# EOG_FRONT_END.net
KiCad netlist of a schematic drawn in Altium Designer
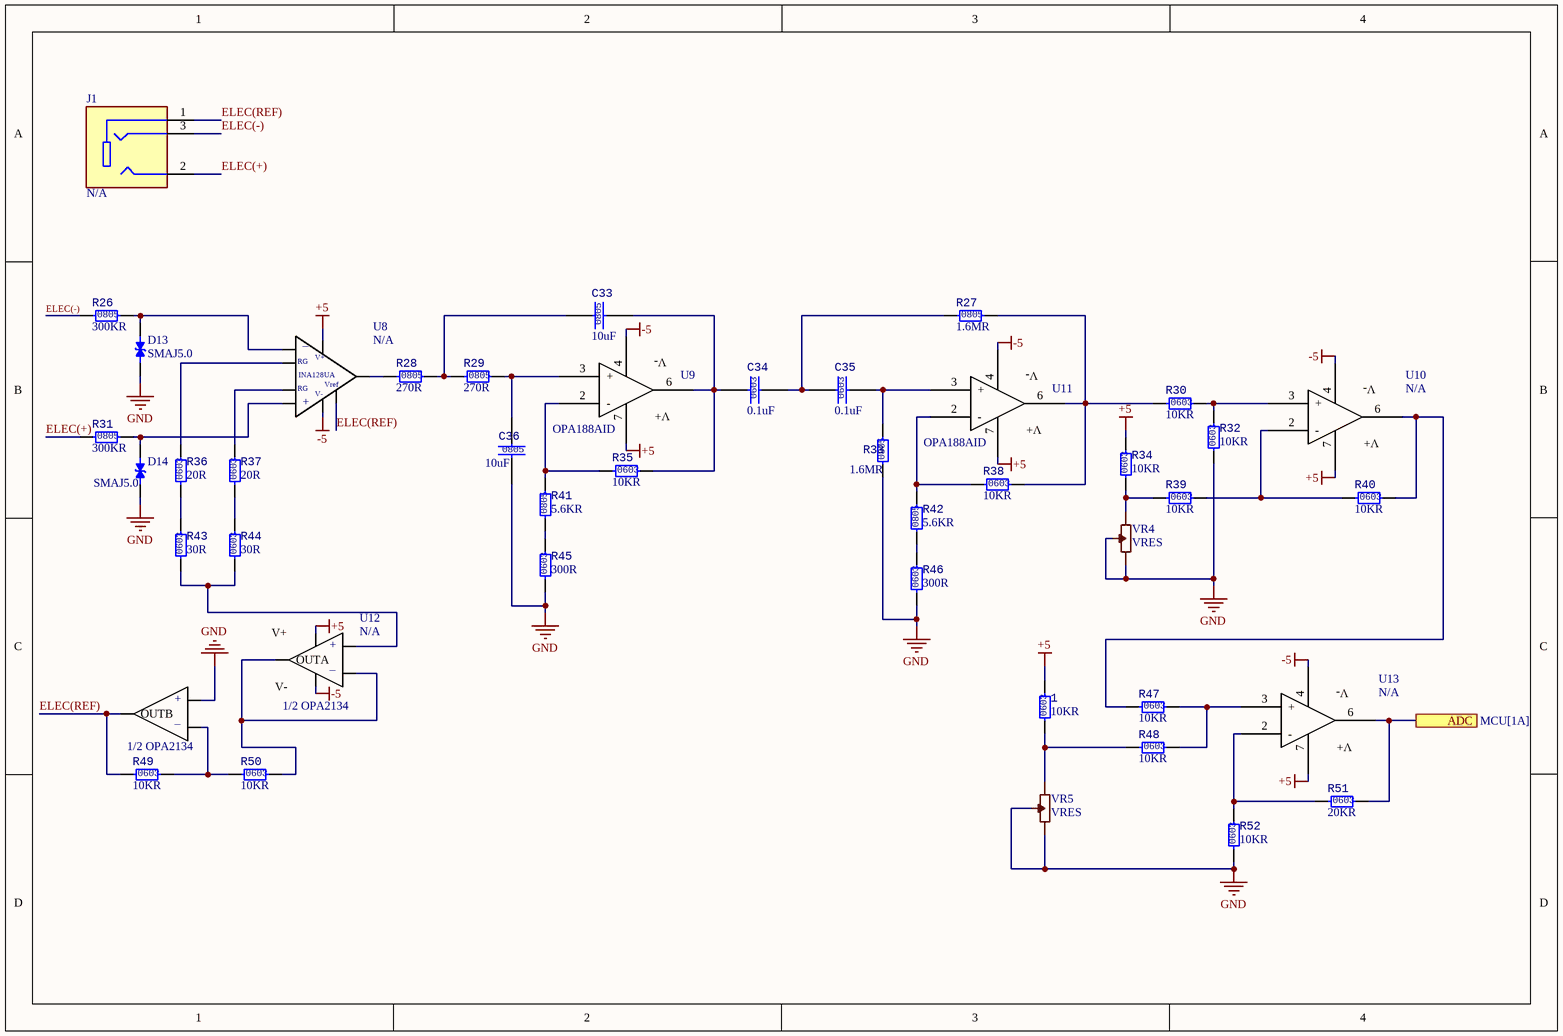
[diagram p0: EOG_FRONT_END.SchDoc]

(export (version "E")
  (design (tool "Eeschema 10.0.6"))
  (components
    (comp (ref "1")
      (value "10KR")
      (footprint "RESC 0603(1608) SMD")
      (description "RESISTOR SMD 10KR OHM 1% 100mW 0603")
      (fields (field (name "SIZE") "0603") (field (name "TOLERANCE") "1%"))
      (libsource (lib "Database_Libs1") (part "RESISTOR"))
    )
    (comp (ref "C33")
      (value "10uF")
      (footprint "CAPCER 0603 SMD")
      (description "CAPACITOR SMD 10uF 25V 10% 0805")
      (fields (field (name "SIZE") "0805") (field (name "TOLERANCE") "10%"))
      (libsource (lib "Database_Libs1") (part "CAPACITOR"))
    )
    (comp (ref "C34")
      (value "0.1uF")
      (footprint "CAPCER 0805 SMD")
      (description "CAPACITOR SMD 0.1uF 50V 10% 0603")
      (fields (field (name "SIZE") "0603") (field (name "TOLERANCE") "10%"))
      (libsource (lib "Database_Libs1") (part "CAPACITOR"))
    )
    (comp (ref "C35")
      (value "0.1uF")
      (footprint "CAPCER 0805 SMD")
      (description "CAPACITOR SMD 0.1uF 50V 10% 0603")
      (fields (field (name "SIZE") "0603") (field (name "TOLERANCE") "10%"))
      (libsource (lib "Database_Libs1") (part "CAPACITOR"))
    )
    (comp (ref "C36")
      (value "10uF")
      (footprint "CAPCER 0603 SMD")
      (description "CAPACITOR SMD 10uF 25V 10% 0805")
      (fields (field (name "SIZE") "0805") (field (name "TOLERANCE") "10%"))
      (libsource (lib "Database_Libs1") (part "CAPACITOR"))
    )
    (comp (ref "D13") (value "SMAJ5.0") (libsource (lib "Database_Libs1") (part "SMAJ5.0")))
    (comp (ref "D14") (value "SMAJ5.0") (libsource (lib "Database_Libs1") (part "SMAJ5.0")))
    (comp (ref "J1")
      (value "N/A")
      (footprint "JACK_3.5")
      (description "Jack Audio 3.5mm PJ-320D PJ320D Hàn Board chân dán")
      (fields (field (name "Comment") "JACK 3.5mm"))
      (libsource (lib "Database_Libs1") (part "JACK_3.5"))
    )
    (comp (ref "R26")
      (value "300KR")
      (footprint "RESC 0805 SMD")
      (description "RESISTOR SMD 300KR OHM 5% 125mW 0805")
      (fields (field (name "SIZE") "0805") (field (name "TOLERANCE") "5%"))
      (libsource (lib "") (part "RESISTOR_1"))
    )
    (comp (ref "R27")
      (value "1.6MR")
      (footprint "RESC 0805 SMD")
      (description "RESISTOR SMD 1.6MR OHM 5% 125mW 0805")
      (fields (field (name "SIZE") "0805") (field (name "TOLERANCE") "5%"))
      (libsource (lib "") (part "RESISTOR_1"))
    )
    (comp (ref "R28")
      (value "270R")
      (footprint "RESC 0805 SMD")
      (description "RESISTOR SMD 270R OHM 5% 125mW 0805")
      (fields (field (name "SIZE") "0805") (field (name "TOLERANCE") "5%"))
      (libsource (lib "") (part "RESISTOR_1"))
    )
    (comp (ref "R29")
      (value "270R")
      (footprint "RESC 0805 SMD")
      (description "RESISTOR SMD 270R OHM 5% 125mW 0805")
      (fields (field (name "SIZE") "0805") (field (name "TOLERANCE") "5%"))
      (libsource (lib "") (part "RESISTOR_1"))
    )
    (comp (ref "R30")
      (value "10KR")
      (footprint "RESC 0603(1608) SMD")
      (description "RESISTOR SMD 10KR OHM 1% 100mW 0603")
      (fields (field (name "SIZE") "0603") (field (name "TOLERANCE") "1%"))
      (libsource (lib "") (part "RESISTOR_1"))
    )
    (comp (ref "R31")
      (value "300KR")
      (footprint "RESC 0805 SMD")
      (description "RESISTOR SMD 300KR OHM 5% 125mW 0805")
      (fields (field (name "SIZE") "0805") (field (name "TOLERANCE") "5%"))
      (libsource (lib "") (part "RESISTOR_1"))
    )
    (comp (ref "R32")
      (value "10KR")
      (footprint "RESC 0603(1608) SMD")
      (description "RESISTOR SMD 10KR OHM 1% 100mW 0603")
      (fields (field (name "SIZE") "0603") (field (name "TOLERANCE") "1%"))
      (libsource (lib "Database_Libs1") (part "RESISTOR"))
    )
    (comp (ref "R33")
      (value "1.6MR")
      (footprint "RESC 0805 SMD")
      (description "RESISTOR SMD 1.6MR OHM 5% 125mW 0805")
      (fields (field (name "SIZE") "0805") (field (name "TOLERANCE") "5%"))
      (libsource (lib "Database_Libs1") (part "RESISTOR"))
    )
    (comp (ref "R34")
      (value "10KR")
      (footprint "RESC 0603(1608) SMD")
      (description "RESISTOR SMD 10KR OHM 1% 100mW 0603")
      (fields (field (name "SIZE") "0603") (field (name "TOLERANCE") "1%"))
      (libsource (lib "Database_Libs1") (part "RESISTOR"))
    )
    (comp (ref "R35")
      (value "10KR")
      (footprint "RESC 0603(1608) SMD")
      (description "RESISTOR SMD 10KR OHM 1% 100mW 0603")
      (fields (field (name "SIZE") "0603") (field (name "TOLERANCE") "1%"))
      (libsource (lib "") (part "RESISTOR_1"))
    )
    (comp (ref "R36")
      (value "20R")
      (footprint "RESC 0603(1608) SMD")
      (description "RESISTOR SMD 510R OHM 1% 100mW 0603")
      (fields (field (name "SIZE") "0603") (field (name "TOLERANCE") "1%") (field (name "Comment") "510R"))
      (libsource (lib "Database_Libs1") (part "RESISTOR"))
    )
    (comp (ref "R37")
      (value "20R")
      (footprint "RESC 0603(1608) SMD")
      (description "RESISTOR SMD 510R OHM 1% 100mW 0603")
      (fields (field (name "SIZE") "0603") (field (name "TOLERANCE") "1%") (field (name "Comment") "510R"))
      (libsource (lib "Database_Libs1") (part "RESISTOR"))
    )
    (comp (ref "R38")
      (value "10KR")
      (footprint "RESC 0603(1608) SMD")
      (description "RESISTOR SMD 10KR OHM 1% 100mW 0603")
      (fields (field (name "SIZE") "0603") (field (name "TOLERANCE") "1%"))
      (libsource (lib "") (part "RESISTOR_1"))
    )
    (comp (ref "R39")
      (value "10KR")
      (footprint "RESC 0603(1608) SMD")
      (description "RESISTOR SMD 10KR OHM 1% 100mW 0603")
      (fields (field (name "SIZE") "0603") (field (name "TOLERANCE") "1%"))
      (libsource (lib "") (part "RESISTOR_1"))
    )
    (comp (ref "R40")
      (value "10KR")
      (footprint "RESC 0603(1608) SMD")
      (description "RESISTOR SMD 10KR OHM 1% 100mW 0603")
      (fields (field (name "SIZE") "0603") (field (name "TOLERANCE") "1%"))
      (libsource (lib "") (part "RESISTOR_1"))
    )
    (comp (ref "R41")
      (value "5.6KR")
      (footprint "RESC 0805 SMD")
      (description "RESISTOR SMD 5.6KR OHM 1% 125mW 0805")
      (fields (field (name "SIZE") "0805") (field (name "TOLERANCE") "1%"))
      (libsource (lib "Database_Libs1") (part "RESISTOR"))
    )
    (comp (ref "R42")
      (value "5.6KR")
      (footprint "RESC 0805 SMD")
      (description "RESISTOR SMD 5.6KR OHM 1% 125mW 0805")
      (fields (field (name "SIZE") "0805") (field (name "TOLERANCE") "1%"))
      (libsource (lib "Database_Libs1") (part "RESISTOR"))
    )
    (comp (ref "R43")
      (value "30R")
      (footprint "RESC 0603(1608) SMD")
      (description "RESISTOR SMD 12KR OHM 1% 100mW 0603")
      (fields (field (name "SIZE") "0603") (field (name "TOLERANCE") "1%") (field (name "Comment") "12KR"))
      (libsource (lib "Database_Libs1") (part "RESISTOR"))
    )
    (comp (ref "R44")
      (value "30R")
      (footprint "RESC 0603(1608) SMD")
      (description "RESISTOR SMD 12KR OHM 1% 100mW 0603")
      (fields (field (name "SIZE") "0603") (field (name "TOLERANCE") "1%") (field (name "Comment") "12KR"))
      (libsource (lib "Database_Libs1") (part "RESISTOR"))
    )
    (comp (ref "R45")
      (value "300R")
      (footprint "RESC 0603(1608) SMD")
      (description "RESISTOR SMD 300R OHM 1% 125mW 0603")
      (fields (field (name "SIZE") "0603") (field (name "TOLERANCE") "1%"))
      (libsource (lib "Database_Libs1") (part "RESISTOR"))
    )
    (comp (ref "R46")
      (value "300R")
      (footprint "RESC 0603(1608) SMD")
      (description "RESISTOR SMD 300R OHM 1% 125mW 0603")
      (fields (field (name "SIZE") "0603") (field (name "TOLERANCE") "1%"))
      (libsource (lib "Database_Libs1") (part "RESISTOR"))
    )
    (comp (ref "R47")
      (value "10KR")
      (footprint "RESC 0603(1608) SMD")
      (description "RESISTOR SMD 10KR OHM 1% 100mW 0603")
      (fields (field (name "SIZE") "0603") (field (name "TOLERANCE") "1%"))
      (libsource (lib "") (part "RESISTOR_1"))
    )
    (comp (ref "R48")
      (value "10KR")
      (footprint "RESC 0603(1608) SMD")
      (description "RESISTOR SMD 10KR OHM 1% 100mW 0603")
      (fields (field (name "SIZE") "0603") (field (name "TOLERANCE") "1%"))
      (libsource (lib "") (part "RESISTOR_1"))
    )
    (comp (ref "R49")
      (value "10KR")
      (footprint "RESC 0603(1608) SMD")
      (description "RESISTOR SMD 10KR OHM 1% 100mW 0603")
      (fields (field (name "SIZE") "0603") (field (name "TOLERANCE") "1%"))
      (libsource (lib "") (part "RESISTOR_1"))
    )
    (comp (ref "R50")
      (value "10KR")
      (footprint "RESC 0603(1608) SMD")
      (description "RESISTOR SMD 10KR OHM 1% 100mW 0603")
      (fields (field (name "SIZE") "0603") (field (name "TOLERANCE") "1%"))
      (libsource (lib "") (part "RESISTOR_1"))
    )
    (comp (ref "R51")
      (value "20KR")
      (footprint "RESC 0603(1608) SMD")
      (description "RESISTOR SMD 10KR OHM 1% 100mW 0603")
      (fields (field (name "SIZE") "0603") (field (name "TOLERANCE") "1%") (field (name "Comment") "10KR"))
      (libsource (lib "") (part "RESISTOR_1"))
    )
    (comp (ref "R52")
      (value "10KR")
      (footprint "RESC 0603(1608) SMD")
      (description "RESISTOR SMD 10KR OHM 1% 100mW 0603")
      (fields (field (name "SIZE") "0603") (field (name "TOLERANCE") "1%"))
      (libsource (lib "Database_Libs1") (part "RESISTOR"))
    )
    (comp (ref "U8")
      (value "N/A")
      (footprint "8-SOIC")
      (description "Instrumentation Amplifier 1 Circuit 8-SOIC")
      (fields (field (name "Comment") "INA128UA"))
      (libsource (lib "Database_Libs1") (part "INA128UA"))
    )
    (comp (ref "U9")
      (value "OPA188AID")
      (footprint "8-SOIC")
      (description "Zero-Drift Amplifier 1 Circuit Rail-to-Rail 8-SOIC")
      (libsource (lib "Database_Libs1") (part "OPA188AID"))
    )
    (comp (ref "U10")
      (value "N/A")
      (footprint "8-SOIC")
      (description "Zero-Drift Amplifier 1 Circuit Rail-to-Rail 8-SOIC")
      (fields (field (name "Comment") "OPA188AID"))
      (libsource (lib "Database_Libs1") (part "OPA188AID"))
    )
    (comp (ref "U11")
      (value "OPA188AID")
      (footprint "8-SOIC")
      (description "Zero-Drift Amplifier 1 Circuit Rail-to-Rail 8-SOIC")
      (libsource (lib "Database_Libs1") (part "OPA188AID"))
    )
    (comp (ref "U12")
      (value "N/A")
      (footprint "8-SOIC")
      (description "IC AUDIO 2 CIRCUIT 8SOIC")
      (fields (field (name "Comment") "OPA2134UA"))
      (libsource (lib "Database_Libs1") (part "OPA2134UA"))
    )
    (comp (ref "U13")
      (value "N/A")
      (footprint "8-SOIC")
      (description "Zero-Drift Amplifier 1 Circuit Rail-to-Rail 8-SOIC")
      (fields (field (name "Comment") "OPA188AID"))
      (libsource (lib "Database_Libs1") (part "OPA188AID"))
    )
    (comp (ref "VR4") (value "VRES") (libsource (lib "Database_Libs1") (part "VRES")))
    (comp (ref "VR5") (value "VRES") (libsource (lib "Database_Libs1") (part "VRES")))
  )
  (nets
    (net (code "1") (name "+5") (class "Default")
      (node (ref "1") (pin "2") (pinfunction "2_2") (pintype "passive"))
      (node (ref "R34") (pin "2") (pinfunction "2_2") (pintype "passive"))
      (node (ref "U10") (pin "7") (pinfunction "VCC_7") (pintype "passive"))
      (node (ref "U11") (pin "7") (pinfunction "VCC_7") (pintype "passive"))
      (node (ref "U12") (pin "8") (pinfunction "V+_8") (pintype "passive"))
      (node (ref "U13") (pin "7") (pinfunction "VCC_7") (pintype "passive"))
      (node (ref "U8") (pin "7") (pinfunction "9_7") (pintype "passive"))
      (node (ref "U9") (pin "7") (pinfunction "VCC_7") (pintype "passive"))
    )
    (net (code "2") (name "-5") (class "Default")
      (node (ref "U10") (pin "4") (pinfunction "GND_4") (pintype "passive"))
      (node (ref "U11") (pin "4") (pinfunction "GND_4") (pintype "passive"))
      (node (ref "U12") (pin "4") (pinfunction "V-_4") (pintype "passive"))
      (node (ref "U13") (pin "4") (pinfunction "GND_4") (pintype "passive"))
      (node (ref "U8") (pin "4") (pinfunction "10_4") (pintype "passive"))
      (node (ref "U9") (pin "4") (pinfunction "GND_4") (pintype "passive"))
    )
    (net (code "3") (name "/ADC") (class "Default")
      (node (ref "R51") (pin "2") (pinfunction "2_2") (pintype "passive"))
      (node (ref "U13") (pin "6") (pinfunction "OUT_1_6") (pintype "passive"))
    )
    (net (code "4") (name "/ELEC(+)") (class "Default")
      (node (ref "J1") (pin "2") (pinfunction "2_2") (pintype "passive"))
      (node (ref "R31") (pin "1") (pinfunction "1_1") (pintype "passive"))
    )
    (net (code "5") (name "/ELEC(-)") (class "Default")
      (node (ref "J1") (pin "3") (pinfunction "3_3") (pintype "passive"))
      (node (ref "R26") (pin "1") (pinfunction "1_1") (pintype "passive"))
    )
    (net (code "6") (name "/ELEC(REF)") (class "Default")
      (node (ref "J1") (pin "1") (pinfunction "1_1") (pintype "passive"))
      (node (ref "R49") (pin "1") (pinfunction "1_1") (pintype "passive"))
      (node (ref "U12") (pin "7") (pinfunction "OUTB_7") (pintype "passive"))
      (node (ref "U8") (pin "5") (pinfunction "11_5") (pintype "passive"))
    )
    (net (code "7") (name "GND") (class "Default")
      (node (ref "C36") (pin "2") (pinfunction "2_2") (pintype "passive"))
      (node (ref "D13") (pin "1") (pinfunction "1_1") (pintype "passive"))
      (node (ref "D14") (pin "1") (pinfunction "1_1") (pintype "passive"))
      (node (ref "R32") (pin "1") (pinfunction "1_1") (pintype "passive"))
      (node (ref "R33") (pin "1") (pinfunction "1_1") (pintype "passive"))
      (node (ref "R45") (pin "1") (pinfunction "1_1") (pintype "passive"))
      (node (ref "R46") (pin "1") (pinfunction "1_1") (pintype "passive"))
      (node (ref "R52") (pin "1") (pinfunction "1_1") (pintype "passive"))
      (node (ref "U12") (pin "5") (pinfunction "INB(+)_5") (pintype "passive"))
      (node (ref "VR4") (pin "1") (pinfunction "1_1") (pintype "passive"))
      (node (ref "VR4") (pin "2") (pinfunction "2_2") (pintype "passive"))
      (node (ref "VR5") (pin "1") (pinfunction "1_1") (pintype "passive"))
      (node (ref "VR5") (pin "2") (pinfunction "2_2") (pintype "passive"))
    )
    (net (code "8") (name "Net-(1-Pad1)") (class "Default")
      (node (ref "1") (pin "1") (pinfunction "1_1") (pintype "passive"))
      (node (ref "R48") (pin "1") (pinfunction "1_1") (pintype "passive"))
      (node (ref "VR5") (pin "3") (pinfunction "3_3") (pintype "passive"))
    )
    (net (code "9") (name "Net-(C33-Pad1)") (class "Default")
      (node (ref "C33") (pin "1") (pinfunction "1_1") (pintype "passive"))
      (node (ref "R28") (pin "2") (pinfunction "2_2") (pintype "passive"))
      (node (ref "R29") (pin "1") (pinfunction "1_1") (pintype "passive"))
    )
    (net (code "10") (name "Net-(C34-Pad2)") (class "Default")
      (node (ref "C34") (pin "2") (pinfunction "2_2") (pintype "passive"))
      (node (ref "C35") (pin "1") (pinfunction "1_1") (pintype "passive"))
      (node (ref "R27") (pin "1") (pinfunction "1_1") (pintype "passive"))
    )
    (net (code "11") (name "Net-(D13-Pad2)") (class "Default")
      (node (ref "D13") (pin "2") (pinfunction "2_2") (pintype "passive"))
      (node (ref "R26") (pin "2") (pinfunction "2_2") (pintype "passive"))
      (node (ref "U8") (pin "2") (pinfunction "10_2") (pintype "passive"))
    )
    (net (code "12") (name "Net-(R28-Pad1)") (class "Default")
      (node (ref "R28") (pin "1") (pinfunction "1_1") (pintype "passive"))
      (node (ref "U8") (pin "6") (pinfunction "9_6") (pintype "passive"))
    )
    (net (code "13") (name "Net-(R34-Pad1)") (class "Default")
      (node (ref "R34") (pin "1") (pinfunction "1_1") (pintype "passive"))
      (node (ref "R39") (pin "1") (pinfunction "1_1") (pintype "passive"))
      (node (ref "VR4") (pin "3") (pinfunction "3_3") (pintype "passive"))
    )
    (net (code "14") (name "Net-(R36-Pad1)") (class "Default")
      (node (ref "R36") (pin "1") (pinfunction "1_1") (pintype "passive"))
      (node (ref "R43") (pin "2") (pinfunction "2_2") (pintype "passive"))
    )
    (net (code "15") (name "Net-(R36-Pad2)") (class "Default")
      (node (ref "R36") (pin "2") (pinfunction "2_2") (pintype "passive"))
      (node (ref "U8") (pin "1") (pinfunction "11_1") (pintype "passive"))
    )
    (net (code "16") (name "Net-(R37-Pad1)") (class "Default")
      (node (ref "R37") (pin "1") (pinfunction "1_1") (pintype "passive"))
      (node (ref "R44") (pin "2") (pinfunction "2_2") (pintype "passive"))
    )
    (net (code "17") (name "Net-(R41-Pad1)") (class "Default")
      (node (ref "R41") (pin "1") (pinfunction "1_1") (pintype "passive"))
      (node (ref "R45") (pin "2") (pinfunction "2_2") (pintype "passive"))
    )
    (net (code "18") (name "Net-(R42-Pad1)") (class "Default")
      (node (ref "R42") (pin "1") (pinfunction "1_1") (pintype "passive"))
      (node (ref "R46") (pin "2") (pinfunction "2_2") (pintype "passive"))
    )
    (net (code "19") (name "Net-(U8-12)") (class "Default")
      (node (ref "R37") (pin "2") (pinfunction "2_2") (pintype "passive"))
      (node (ref "U8") (pin "8") (pinfunction "12_8") (pintype "passive"))
    )
    (net (code "20") (name "Net-(U8-13)") (class "Default")
      (node (ref "D14") (pin "2") (pinfunction "2_2") (pintype "passive"))
      (node (ref "R31") (pin "2") (pinfunction "2_2") (pintype "passive"))
      (node (ref "U8") (pin "3") (pinfunction "13_3") (pintype "passive"))
    )
    (net (code "21") (name "Net-(U9-+)") (class "Default")
      (node (ref "C36") (pin "1") (pinfunction "1_1") (pintype "passive"))
      (node (ref "R29") (pin "2") (pinfunction "2_2") (pintype "passive"))
      (node (ref "U9") (pin "3") (pinfunction "+_3") (pintype "passive"))
    )
    (net (code "22") (name "Net-(U9--)") (class "Default")
      (node (ref "R35") (pin "1") (pinfunction "1_1") (pintype "passive"))
      (node (ref "R41") (pin "2") (pinfunction "2_2") (pintype "passive"))
      (node (ref "U9") (pin "2") (pinfunction "-_2") (pintype "passive"))
    )
    (net (code "23") (name "Net-(U9-OUT_1)") (class "Default")
      (node (ref "C33") (pin "2") (pinfunction "2_2") (pintype "passive"))
      (node (ref "C34") (pin "1") (pinfunction "1_1") (pintype "passive"))
      (node (ref "R35") (pin "2") (pinfunction "2_2") (pintype "passive"))
      (node (ref "U9") (pin "6") (pinfunction "OUT_1_6") (pintype "passive"))
    )
    (net (code "24") (name "Net-(U10-+)") (class "Default")
      (node (ref "R30") (pin "2") (pinfunction "2_2") (pintype "passive"))
      (node (ref "R32") (pin "2") (pinfunction "2_2") (pintype "passive"))
      (node (ref "U10") (pin "3") (pinfunction "+_3") (pintype "passive"))
    )
    (net (code "25") (name "Net-(U10--)") (class "Default")
      (node (ref "R39") (pin "2") (pinfunction "2_2") (pintype "passive"))
      (node (ref "R40") (pin "1") (pinfunction "1_1") (pintype "passive"))
      (node (ref "U10") (pin "2") (pinfunction "-_2") (pintype "passive"))
    )
    (net (code "26") (name "Net-(U10-OUT_1)") (class "Default")
      (node (ref "R40") (pin "2") (pinfunction "2_2") (pintype "passive"))
      (node (ref "R47") (pin "1") (pinfunction "1_1") (pintype "passive"))
      (node (ref "U10") (pin "6") (pinfunction "OUT_1_6") (pintype "passive"))
    )
    (net (code "27") (name "Net-(U11-+)") (class "Default")
      (node (ref "C35") (pin "2") (pinfunction "2_2") (pintype "passive"))
      (node (ref "R33") (pin "2") (pinfunction "2_2") (pintype "passive"))
      (node (ref "U11") (pin "3") (pinfunction "+_3") (pintype "passive"))
    )
    (net (code "28") (name "Net-(U11--)") (class "Default")
      (node (ref "R38") (pin "1") (pinfunction "1_1") (pintype "passive"))
      (node (ref "R42") (pin "2") (pinfunction "2_2") (pintype "passive"))
      (node (ref "U11") (pin "2") (pinfunction "-_2") (pintype "passive"))
    )
    (net (code "29") (name "Net-(U11-OUT_1)") (class "Default")
      (node (ref "R27") (pin "2") (pinfunction "2_2") (pintype "passive"))
      (node (ref "R30") (pin "1") (pinfunction "1_1") (pintype "passive"))
      (node (ref "R38") (pin "2") (pinfunction "2_2") (pintype "passive"))
      (node (ref "U11") (pin "6") (pinfunction "OUT_1_6") (pintype "passive"))
    )
    (net (code "30") (name "Net-(U12-INA(+))") (class "Default")
      (node (ref "R43") (pin "1") (pinfunction "1_1") (pintype "passive"))
      (node (ref "R44") (pin "1") (pinfunction "1_1") (pintype "passive"))
      (node (ref "U12") (pin "2") (pinfunction "INA(+)_2") (pintype "passive"))
    )
    (net (code "31") (name "Net-(U12-INA(-))") (class "Default")
      (node (ref "R50") (pin "2") (pinfunction "2_2") (pintype "passive"))
      (node (ref "U12") (pin "1") (pinfunction "OUTA_1") (pintype "passive"))
      (node (ref "U12") (pin "3") (pinfunction "INA(-)_3") (pintype "passive"))
    )
    (net (code "32") (name "Net-(U12-INB(-))") (class "Default")
      (node (ref "R49") (pin "2") (pinfunction "2_2") (pintype "passive"))
      (node (ref "R50") (pin "1") (pinfunction "1_1") (pintype "passive"))
      (node (ref "U12") (pin "6") (pinfunction "INB(-)_6") (pintype "passive"))
    )
    (net (code "33") (name "Net-(U13-+)") (class "Default")
      (node (ref "R47") (pin "2") (pinfunction "2_2") (pintype "passive"))
      (node (ref "R48") (pin "2") (pinfunction "2_2") (pintype "passive"))
      (node (ref "U13") (pin "3") (pinfunction "+_3") (pintype "passive"))
    )
    (net (code "34") (name "Net-(U13--)") (class "Default")
      (node (ref "R51") (pin "1") (pinfunction "1_1") (pintype "passive"))
      (node (ref "R52") (pin "2") (pinfunction "2_2") (pintype "passive"))
      (node (ref "U13") (pin "2") (pinfunction "-_2") (pintype "passive"))
    )
  )
)
